# InterlockControl.net
KiCad netlist of a schematic drawn in Altium Designer
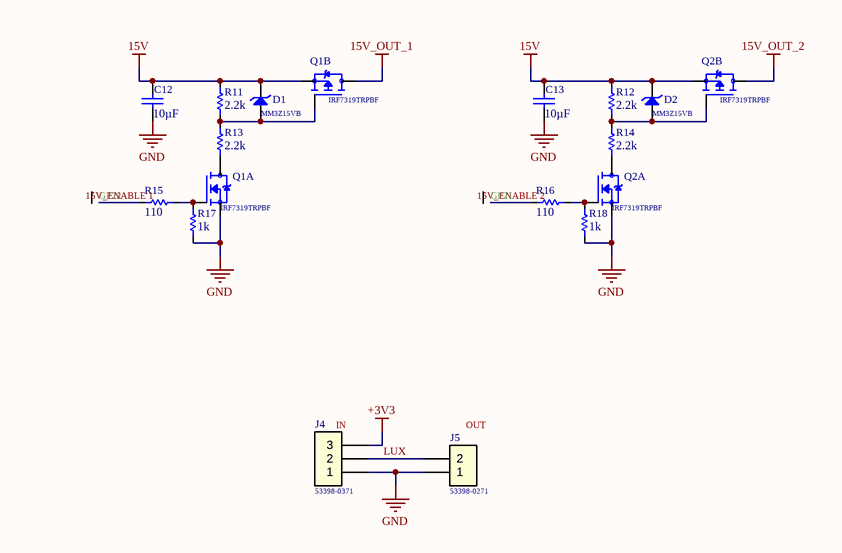
[diagram p0: InterlockControl.SchDoc]

(export (version "E")
  (design (tool "Eeschema 10.0.6"))
  (components
    (comp (ref "C12")
      (value "10µF")
      (footprint "CAPC3225X279X50NL20T25")
      (description "10uF ±10% 50V Ceramic Capacitor X7R 1210 (3225 Metric)")
      (fields (field (name "TOLERANCE") "10%") (field (name "Comment") "C1210-10uF-50V-10%-X7R"))
      (libsource (lib "Sainsbury Wellcome Centre") (part "Cap"))
    )
    (comp (ref "C13")
      (value "10µF")
      (footprint "CAPC3225X279X50NL20T25")
      (description "10uF ±10% 50V Ceramic Capacitor X7R 1210 (3225 Metric)")
      (fields (field (name "TOLERANCE") "10%") (field (name "Comment") "C1210-10uF-50V-10%-X7R"))
      (libsource (lib "Sainsbury Wellcome Centre") (part "Cap"))
    )
    (comp (ref "D1")
      (value "MM3Z15VB")
      (footprint "SODFL250X100-2N")
      (description "Zener Diode, 15V V(Z), 2%, 0.2W, Silicon, Unidirectional")
      (fields (field (name "PARTNUMBER") "MM3Z5V1B"))
      (libsource (lib "Sainsbury Wellcome Centre") (part "Zener-A1C2"))
    )
    (comp (ref "D2")
      (value "MM3Z15VB")
      (footprint "SODFL250X100-2N")
      (description "Zener Diode, 15V V(Z), 2%, 0.2W, Silicon, Unidirectional")
      (fields (field (name "PARTNUMBER") "MM3Z5V1B"))
      (libsource (lib "Sainsbury Wellcome Centre") (part "Zener-A1C2"))
    )
    (comp (ref "J4")
      (value "53398-0371")
      (footprint "MOLX-53398-0371_V")
      (libsource (lib "Sainsbury Wellcome Centre") (part "Jack 3x1"))
    )
    (comp (ref "J5")
      (value "53398-0271")
      (footprint "MOLX-53398-0271_V")
      (libsource (lib "Sainsbury Wellcome Centre") (part "Jack 2x1"))
    )
    (comp (ref "Q1")
      (value "IRF7319TRPBF")
      (footprint "SOIC127P600X175-8N")
      (libsource (lib "Sainsbury Wellcome Centre") (part "IRF7319TRPBF"))
    )
    (comp (ref "Q2")
      (value "IRF7319TRPBF")
      (footprint "SOIC127P600X175-8N")
      (libsource (lib "Sainsbury Wellcome Centre") (part "IRF7319TRPBF"))
    )
    (comp (ref "R11")
      (value "2.2k")
      (footprint "FP-CPF0603-IPC_B")
      (description "Surface Mount Resistor 2.2k Ohm 1/16 W 0.1% 0603 (1608 Metric)")
      (fields (field (name "TOLERANCE") "0.1%") (field (name "Comment") "R0603-2k2-1/16W-0.1%"))
      (libsource (lib "Sainsbury Wellcome Centre") (part "Res"))
    )
    (comp (ref "R12")
      (value "2.2k")
      (footprint "FP-CPF0603-IPC_B")
      (description "Surface Mount Resistor 2.2k Ohm 1/16 W 0.1% 0603 (1608 Metric)")
      (fields (field (name "TOLERANCE") "0.1%") (field (name "Comment") "R0603-2k2-1/16W-0.1%"))
      (libsource (lib "Sainsbury Wellcome Centre") (part "Res"))
    )
    (comp (ref "R13")
      (value "2.2k")
      (footprint "FP-CPF0603-IPC_B")
      (description "Surface Mount Resistor 2.2k Ohm 1/16 W 0.1% 0603 (1608 Metric)")
      (fields (field (name "TOLERANCE") "0.1%") (field (name "Comment") "R0603-2k2-1/16W-0.1%"))
      (libsource (lib "Sainsbury Wellcome Centre") (part "Res"))
    )
    (comp (ref "R14")
      (value "2.2k")
      (footprint "FP-CPF0603-IPC_B")
      (description "Surface Mount Resistor 2.2k Ohm 1/16 W 0.1% 0603 (1608 Metric)")
      (fields (field (name "TOLERANCE") "0.1%") (field (name "Comment") "R0603-2k2-1/16W-0.1%"))
      (libsource (lib "Sainsbury Wellcome Centre") (part "Res"))
    )
    (comp (ref "R15")
      (value "110")
      (footprint "FP-CPF0603-IPC_B")
      (description "Surface Mount Resistor 110 Ohm 1/16 W 0.1% 0603 (1608 Metric)")
      (fields (field (name "TOLERANCE") "0.1%") (field (name "Comment") "R0603-110R-1/16W-0.1%"))
      (libsource (lib "Sainsbury Wellcome Centre") (part "Res"))
    )
    (comp (ref "R16")
      (value "110")
      (footprint "FP-CPF0603-IPC_B")
      (description "Surface Mount Resistor 110 Ohm 1/16 W 0.1% 0603 (1608 Metric)")
      (fields (field (name "TOLERANCE") "0.1%") (field (name "Comment") "R0603-110R-1/16W-0.1%"))
      (libsource (lib "Sainsbury Wellcome Centre") (part "Res"))
    )
    (comp (ref "R17")
      (value "1k")
      (footprint "FP-CPF0603-IPC_B")
      (description "Surface Mount Resistor 1k Ohm 1/16 W 0.1% 0603 (1608 Metric)")
      (fields (field (name "TOLERANCE") "0.1%") (field (name "Comment") "R0603-1k-1/16W-0.1%"))
      (libsource (lib "Sainsbury Wellcome Centre") (part "Res"))
    )
    (comp (ref "R18")
      (value "1k")
      (footprint "FP-CPF0603-IPC_B")
      (description "Surface Mount Resistor 1k Ohm 1/16 W 0.1% 0603 (1608 Metric)")
      (fields (field (name "TOLERANCE") "0.1%") (field (name "Comment") "R0603-1k-1/16W-0.1%"))
      (libsource (lib "Sainsbury Wellcome Centre") (part "Res"))
    )
  )
  (nets
    (net (code "1") (name "+3V3") (class "Default")
      (node (ref "J4") (pin "3") (pinfunction "3_3") (pintype "passive"))
    )
    (net (code "2") (name "/GP21") (class "Default")
      (node (ref "R16") (pin "1") (pinfunction "1_1") (pintype "passive"))
    )
    (net (code "3") (name "/GP22") (class "Default")
      (node (ref "R15") (pin "1") (pinfunction "1_1") (pintype "passive"))
    )
    (net (code "4") (name "/LUX") (class "Default")
      (node (ref "J4") (pin "2") (pinfunction "2_2") (pintype "passive"))
      (node (ref "J5") (pin "2") (pinfunction "2_2") (pintype "passive"))
    )
    (net (code "5") (name "15V") (class "Default")
      (node (ref "C12") (pin "2") (pinfunction "2_2") (pintype "passive"))
      (node (ref "C13") (pin "2") (pinfunction "2_2") (pintype "passive"))
      (node (ref "D1") (pin "2") (pinfunction "C_2") (pintype "passive"))
      (node (ref "D2") (pin "2") (pinfunction "C_2") (pintype "passive"))
      (node (ref "Q1") (pin "3") (pinfunction "S_3") (pintype "passive"))
      (node (ref "Q2") (pin "3") (pinfunction "S_3") (pintype "passive"))
      (node (ref "R11") (pin "2") (pinfunction "2_2") (pintype "passive"))
      (node (ref "R12") (pin "2") (pinfunction "2_2") (pintype "passive"))
    )
    (net (code "6") (name "15V_OUT_1") (class "Default")
      (node (ref "Q1") (pin "5") (pinfunction "D_5") (pintype "passive"))
    )
    (net (code "7") (name "15V_OUT_2") (class "Default")
      (node (ref "Q2") (pin "5") (pinfunction "D_5") (pintype "passive"))
    )
    (net (code "8") (name "GND") (class "Default")
      (node (ref "C12") (pin "1") (pinfunction "1_1") (pintype "passive"))
      (node (ref "C13") (pin "1") (pinfunction "1_1") (pintype "passive"))
      (node (ref "J4") (pin "1") (pinfunction "1_1") (pintype "passive"))
      (node (ref "J5") (pin "1") (pinfunction "1_1") (pintype "passive"))
      (node (ref "Q1") (pin "1") (pinfunction "S_1") (pintype "passive"))
      (node (ref "Q2") (pin "1") (pinfunction "S_1") (pintype "passive"))
      (node (ref "R17") (pin "1") (pinfunction "1_1") (pintype "passive"))
      (node (ref "R18") (pin "1") (pinfunction "1_1") (pintype "passive"))
    )
    (net (code "9") (name "Net-(D1-A)") (class "Default")
      (node (ref "D1") (pin "1") (pinfunction "A_1") (pintype "passive"))
      (node (ref "Q1") (pin "4") (pinfunction "G_4") (pintype "passive"))
      (node (ref "R11") (pin "1") (pinfunction "1_1") (pintype "passive"))
      (node (ref "R13") (pin "2") (pinfunction "2_2") (pintype "passive"))
    )
    (net (code "10") (name "Net-(D2-A)") (class "Default")
      (node (ref "D2") (pin "1") (pinfunction "A_1") (pintype "passive"))
      (node (ref "Q2") (pin "4") (pinfunction "G_4") (pintype "passive"))
      (node (ref "R12") (pin "1") (pinfunction "1_1") (pintype "passive"))
      (node (ref "R14") (pin "2") (pinfunction "2_2") (pintype "passive"))
    )
    (net (code "11") (name "Net-(Q1A-D)") (class "Default")
      (node (ref "Q1") (pin "7") (pinfunction "D_7") (pintype "passive"))
      (node (ref "R13") (pin "1") (pinfunction "1_1") (pintype "passive"))
    )
    (net (code "12") (name "Net-(Q1A-G)") (class "Default")
      (node (ref "Q1") (pin "2") (pinfunction "G_2") (pintype "passive"))
      (node (ref "R15") (pin "2") (pinfunction "2_2") (pintype "passive"))
      (node (ref "R17") (pin "2") (pinfunction "2_2") (pintype "passive"))
    )
    (net (code "13") (name "Net-(Q2A-D)") (class "Default")
      (node (ref "Q2") (pin "7") (pinfunction "D_7") (pintype "passive"))
      (node (ref "R14") (pin "1") (pinfunction "1_1") (pintype "passive"))
    )
    (net (code "14") (name "Net-(Q2A-G)") (class "Default")
      (node (ref "Q2") (pin "2") (pinfunction "G_2") (pintype "passive"))
      (node (ref "R16") (pin "2") (pinfunction "2_2") (pintype "passive"))
      (node (ref "R18") (pin "2") (pinfunction "2_2") (pintype "passive"))
    )
  )
)
